# Home_automation.net
KiCad netlist of a schematic drawn in EAGLE
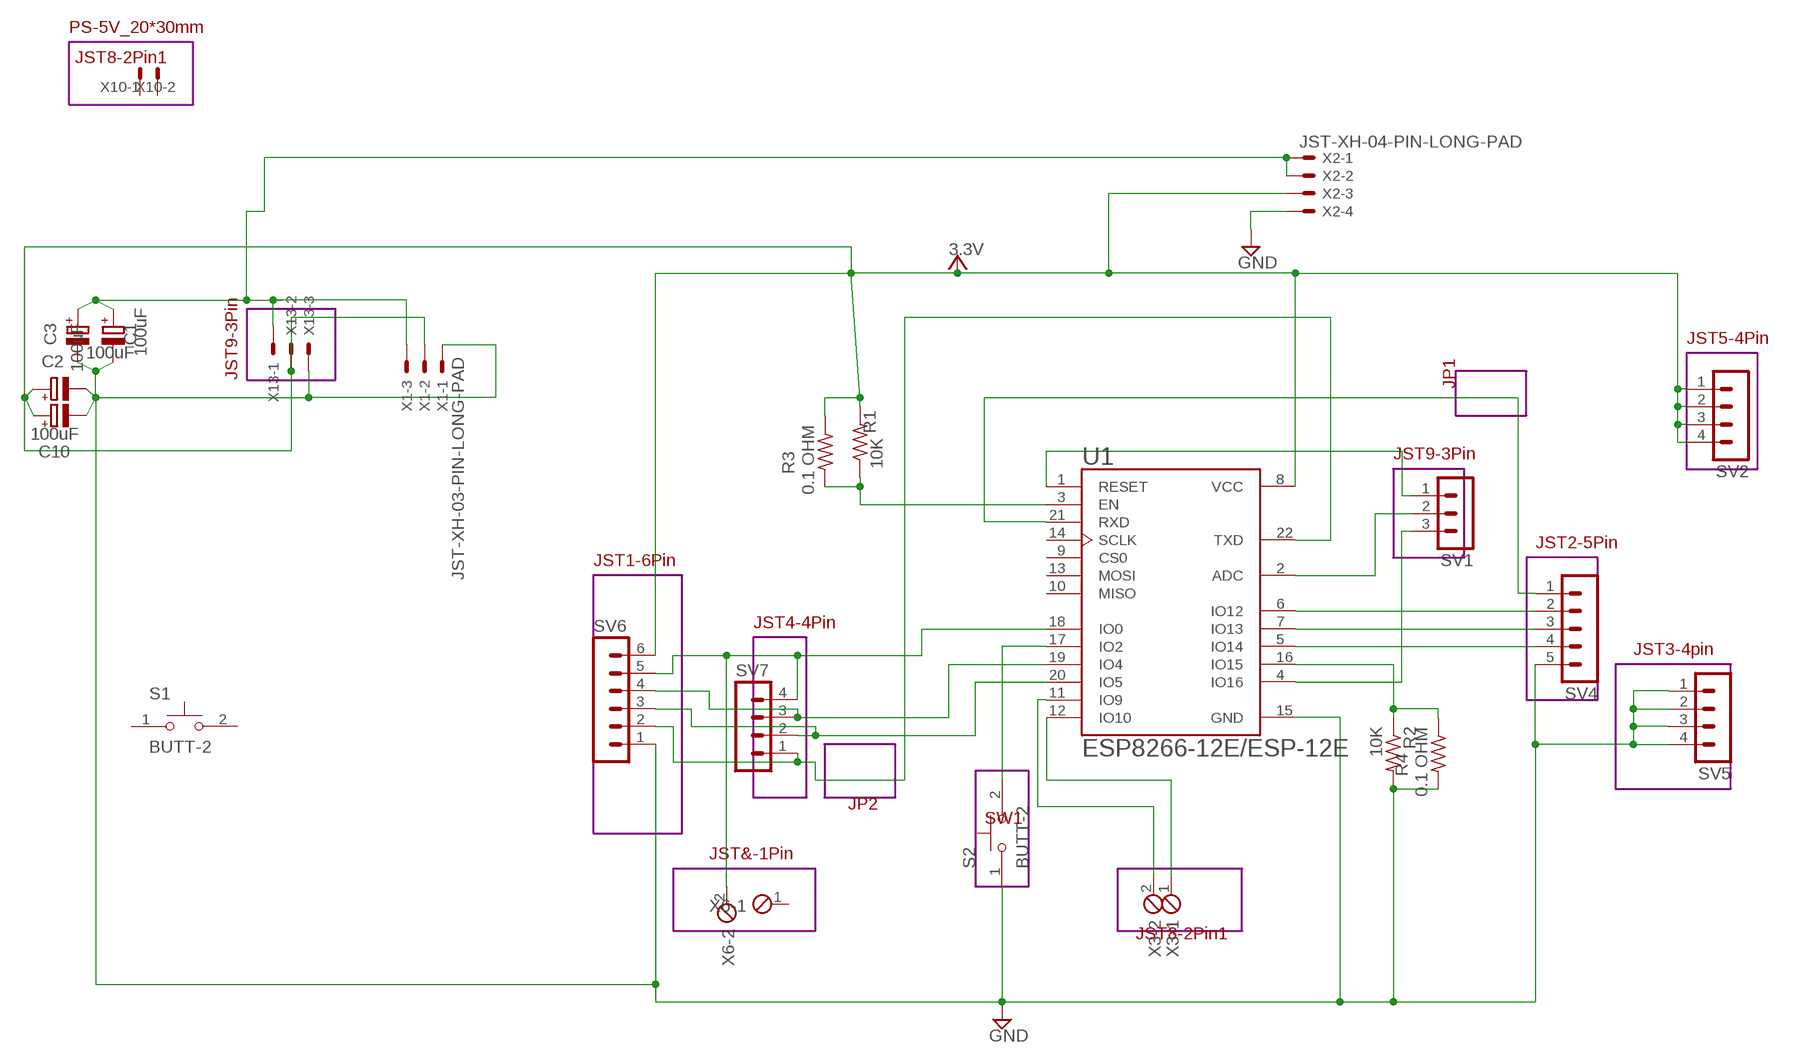
[diagram p0: schematic, sheet 1]

(export (version "E")
  (design (tool "Eeschema 10.0.6"))
  (components
    (comp (ref "C1")
      (value "100uF")
      (footprint "eagle-import:SMC_B")
      (libsource (lib "eagle-import") (part "CPOL-EUSMCB"))
    )
    (comp (ref "C2")
      (value "100uF")
      (footprint "eagle-import:E2,5-6E")
      (libsource (lib "eagle-import") (part "CPOL-EUE2,5-6E"))
    )
    (comp (ref "C3")
      (value "100uF")
      (footprint "eagle-import:E2,5-6E")
      (libsource (lib "eagle-import") (part "CPOL-EUE2,5-6E"))
    )
    (comp (ref "C10")
      (value "100uF")
      (footprint "eagle-import:SMC_B")
      (libsource (lib "eagle-import") (part "CPOL-EUSMCB"))
    )
    (comp (ref "R1")
      (value "10K")
      (footprint "eagle-import:R0805")
      (libsource (lib "eagle-import") (part "R-US_R0805"))
    )
    (comp (ref "R2")
      (value "10K")
      (footprint "eagle-import:R0805")
      (libsource (lib "eagle-import") (part "R-US_R0805"))
    )
    (comp (ref "R3")
      (value "0.1 OHM")
      (footprint "eagle-import:0207_10")
      (libsource (lib "eagle-import") (part "R-US_0207/10"))
    )
    (comp (ref "R4")
      (value "0.1 OHM")
      (footprint "eagle-import:0207_10")
      (libsource (lib "eagle-import") (part "R-US_0207/10"))
    )
    (comp (ref "S1")
      (value "BUTT-2")
      (footprint "eagle-import:SW_BUTT-2")
      (fields (field (name "MF") "Gravitech"))
      (libsource (lib "eagle-import") (part "BUTT-2__BUTT-2"))
    )
    (comp (ref "S2")
      (value "BUTT-2")
      (footprint "eagle-import:SW_BUTT-2")
      (fields (field (name "MF") "Gravitech"))
      (libsource (lib "eagle-import") (part "BUTT-2"))
    )
    (comp (ref "SV1")
      (value "MA03-1")
      (footprint "eagle-import:MA03-1")
      (libsource (lib "eagle-import") (part "MA03-1"))
    )
    (comp (ref "SV2")
      (value "MA04-1")
      (footprint "eagle-import:MA04-1")
      (libsource (lib "eagle-import") (part "MA04-1"))
    )
    (comp (ref "SV4")
      (value "MA05-1")
      (footprint "eagle-import:MA05-1")
      (libsource (lib "eagle-import") (part "MA05-1"))
    )
    (comp (ref "SV5")
      (value "MA04-1")
      (footprint "eagle-import:MA04-1")
      (libsource (lib "eagle-import") (part "MA04-1"))
    )
    (comp (ref "SV6")
      (value "MA06-1")
      (footprint "eagle-import:MA06-1")
      (libsource (lib "eagle-import") (part "MA06-1"))
    )
    (comp (ref "SV7")
      (value "MA04-1")
      (footprint "eagle-import:MA04-1")
      (libsource (lib "eagle-import") (part "MA04-1"))
    )
    (comp (ref "U1")
      (value "ESP8266-12E/ESP-12E")
      (footprint "eagle-import:XCVR_ESP8266-12E_ESP-12E")
      (fields (field (name "MF") "AI-Thinker"))
      (libsource (lib "eagle-import") (part "ESP8266-12E/ESP-12E"))
    )
    (comp (ref "X1")
      (value "JST-XH-03-PIN-LONG-PAD")
      (footprint "eagle-import:JST-XH-03-PACKAGE-LONG-PAD")
      (libsource (lib "eagle-import") (part "JST-XH-03-PIN-LONG-PAD"))
    )
    (comp (ref "X2")
      (value "JST-XH-04-PIN-LONG-PAD")
      (footprint "eagle-import:JST-XH-04-PACKAGE-LONG-PAD")
      (libsource (lib "eagle-import") (part "JST-XH-04-PIN-LONG-PAD"))
    )
    (comp (ref "X3")
      (value "MPT2")
      (footprint "eagle-import:2POL254")
      (libsource (lib "eagle-import") (part "MPT2"))
    )
    (comp (ref "X6")
      (value "MPT2")
      (footprint "eagle-import:2POL254")
      (libsource (lib "eagle-import") (part "MPT2"))
    )
    (comp (ref "X10")
      (value "JST-XH-02-PIN-LONG-PAD")
      (footprint "eagle-import:JST-XH-02-PACKAGE-LONG-PAD")
      (libsource (lib "eagle-import") (part "JST-XH-02-PIN-LONG-PAD"))
    )
    (comp (ref "X13")
      (value "JST9-3Pin")
      (footprint "eagle-import:JST-XH-03-PACKAGE-LONG-PAD")
      (libsource (lib "eagle-import") (part "JST-XH-03-PIN-LONG-PAD"))
    )
  )
  (nets
    (net (code "1") (name "3.3V") (class "Default")
      (node (ref "C10") (pin "+") (pinfunction "+_+") (pintype "passive"))
      (node (ref "C2") (pin "+") (pinfunction "+_+") (pintype "passive"))
      (node (ref "R1") (pin "2") (pinfunction "2_2") (pintype "passive"))
      (node (ref "R3") (pin "1") (pinfunction "1_1") (pintype "passive"))
      (node (ref "SV2") (pin "1") (pinfunction "1_1") (pintype "passive"))
      (node (ref "SV2") (pin "2") (pinfunction "2_2") (pintype "passive"))
      (node (ref "SV2") (pin "3") (pinfunction "3_3") (pintype "passive"))
      (node (ref "SV2") (pin "4") (pinfunction "4_4") (pintype "passive"))
      (node (ref "SV6") (pin "6") (pinfunction "6_6") (pintype "passive"))
      (node (ref "U1") (pin "8") (pinfunction "VCC_8") (pintype "power_in"))
      (node (ref "X1") (pin "2") (pinfunction "S_2") (pintype "passive"))
      (node (ref "X13") (pin "2") (pinfunction "S_2") (pintype "passive"))
      (node (ref "X2") (pin "3") (pinfunction "S_3") (pintype "passive"))
    )
    (net (code "2") (name "GND") (class "Default")
      (node (ref "C1") (pin "-") (pinfunction "-_-") (pintype "passive"))
      (node (ref "C10") (pin "-") (pinfunction "-_-") (pintype "passive"))
      (node (ref "C2") (pin "-") (pinfunction "-_-") (pintype "passive"))
      (node (ref "C3") (pin "-") (pinfunction "-_-") (pintype "passive"))
      (node (ref "R2") (pin "2") (pinfunction "2_2") (pintype "passive"))
      (node (ref "R4") (pin "2") (pinfunction "2_2") (pintype "passive"))
      (node (ref "S2") (pin "1") (pinfunction "1_1") (pintype "passive"))
      (node (ref "SV4") (pin "5") (pinfunction "5_5") (pintype "passive"))
      (node (ref "SV5") (pin "1") (pinfunction "1_1") (pintype "passive"))
      (node (ref "SV5") (pin "2") (pinfunction "2_2") (pintype "passive"))
      (node (ref "SV5") (pin "3") (pinfunction "3_3") (pintype "passive"))
      (node (ref "SV5") (pin "4") (pinfunction "4_4") (pintype "passive"))
      (node (ref "SV6") (pin "1") (pinfunction "1_1") (pintype "passive"))
      (node (ref "U1") (pin "15") (pinfunction "GND_15") (pintype "power_in"))
      (node (ref "X1") (pin "1") (pinfunction "S_1") (pintype "passive"))
      (node (ref "X13") (pin "3") (pinfunction "S_3") (pintype "passive"))
      (node (ref "X2") (pin "4") (pinfunction "S_4") (pintype "passive"))
    )
    (net (code "3") (name "Net-(U1-ADC)") (class "Default")
      (node (ref "SV1") (pin "2") (pinfunction "2_2") (pintype "passive"))
      (node (ref "U1") (pin "2") (pinfunction "ADC_2") (pintype "passive"))
    )
    (net (code "4") (name "Net-(U1-EN)") (class "Default")
      (node (ref "R1") (pin "1") (pinfunction "1_1") (pintype "passive"))
      (node (ref "R3") (pin "2") (pinfunction "2_2") (pintype "passive"))
      (node (ref "U1") (pin "3") (pinfunction "EN_3") (pintype "input"))
    )
    (net (code "5") (name "Net-(U1-IO0)") (class "Default")
      (node (ref "SV6") (pin "5") (pinfunction "5_5") (pintype "passive"))
      (node (ref "SV7") (pin "4") (pinfunction "4_4") (pintype "passive"))
      (node (ref "U1") (pin "18") (pinfunction "IO0_18") (pintype "bidirectional"))
      (node (ref "X6") (pin "2") (pinfunction "1_2") (pintype "passive"))
    )
    (net (code "6") (name "Net-(U1-IO2)") (class "Default")
      (node (ref "S2") (pin "2") (pinfunction "2_2") (pintype "passive"))
      (node (ref "U1") (pin "17") (pinfunction "IO2_17") (pintype "bidirectional"))
    )
    (net (code "7") (name "Net-(U1-IO4)") (class "Default")
      (node (ref "SV6") (pin "4") (pinfunction "4_4") (pintype "passive"))
      (node (ref "SV7") (pin "3") (pinfunction "3_3") (pintype "passive"))
      (node (ref "U1") (pin "19") (pinfunction "IO4_19") (pintype "bidirectional"))
    )
    (net (code "8") (name "Net-(U1-IO5)") (class "Default")
      (node (ref "SV6") (pin "3") (pinfunction "3_3") (pintype "passive"))
      (node (ref "SV7") (pin "2") (pinfunction "2_2") (pintype "passive"))
      (node (ref "U1") (pin "20") (pinfunction "IO5_20") (pintype "bidirectional"))
    )
    (net (code "9") (name "Net-(U1-IO9)") (class "Default")
      (node (ref "U1") (pin "11") (pinfunction "IO9_11") (pintype "bidirectional"))
      (node (ref "X3") (pin "2") (pinfunction "1_2") (pintype "passive"))
    )
    (net (code "10") (name "Net-(U1-IO10)") (class "Default")
      (node (ref "U1") (pin "12") (pinfunction "IO10_12") (pintype "bidirectional"))
      (node (ref "X3") (pin "1") (pinfunction "1_1") (pintype "passive"))
    )
    (net (code "11") (name "Net-(U1-IO12)") (class "Default")
      (node (ref "SV4") (pin "2") (pinfunction "2_2") (pintype "passive"))
      (node (ref "U1") (pin "6") (pinfunction "IO12_6") (pintype "bidirectional"))
    )
    (net (code "12") (name "Net-(U1-IO13)") (class "Default")
      (node (ref "SV4") (pin "3") (pinfunction "3_3") (pintype "passive"))
      (node (ref "U1") (pin "7") (pinfunction "IO13_7") (pintype "bidirectional"))
    )
    (net (code "13") (name "Net-(U1-IO14)") (class "Default")
      (node (ref "SV4") (pin "4") (pinfunction "4_4") (pintype "passive"))
      (node (ref "U1") (pin "5") (pinfunction "IO14_5") (pintype "bidirectional"))
    )
    (net (code "14") (name "Net-(U1-IO15)") (class "Default")
      (node (ref "R2") (pin "1") (pinfunction "1_1") (pintype "passive"))
      (node (ref "R4") (pin "1") (pinfunction "1_1") (pintype "passive"))
      (node (ref "U1") (pin "16") (pinfunction "IO15_16") (pintype "bidirectional"))
    )
    (net (code "15") (name "Net-(U1-IO16)") (class "Default")
      (node (ref "SV1") (pin "3") (pinfunction "3_3") (pintype "passive"))
      (node (ref "U1") (pin "4") (pinfunction "IO16_4") (pintype "bidirectional"))
    )
    (net (code "16") (name "Net-(U1-RESET)") (class "Default")
      (node (ref "SV1") (pin "1") (pinfunction "1_1") (pintype "passive"))
      (node (ref "U1") (pin "1") (pinfunction "RESET_1") (pintype "input"))
    )
    (net (code "17") (name "Net-(U1-RXD)") (class "Default")
      (node (ref "SV4") (pin "1") (pinfunction "1_1") (pintype "passive"))
      (node (ref "U1") (pin "21") (pinfunction "RXD_21") (pintype "input"))
    )
    (net (code "18") (name "Net-(U1-TXD)") (class "Default")
      (node (ref "SV6") (pin "2") (pinfunction "2_2") (pintype "passive"))
      (node (ref "SV7") (pin "1") (pinfunction "1_1") (pintype "passive"))
      (node (ref "U1") (pin "22") (pinfunction "TXD_22") (pintype "output"))
    )
    (net (code "19") (name "Net-(X13A-S)") (class "Default")
      (node (ref "C1") (pin "+") (pinfunction "+_+") (pintype "passive"))
      (node (ref "C3") (pin "+") (pinfunction "+_+") (pintype "passive"))
      (node (ref "X1") (pin "3") (pinfunction "S_3") (pintype "passive"))
      (node (ref "X13") (pin "1") (pinfunction "S_1") (pintype "passive"))
      (node (ref "X2") (pin "1") (pinfunction "S_1") (pintype "passive"))
      (node (ref "X2") (pin "2") (pinfunction "S_2") (pintype "passive"))
    )
    (net (code "20") (name "unconnected-(S1-Pad1)") (class "Default")
      (node (ref "S1") (pin "1") (pinfunction "1_1") (pintype "passive"))
    )
    (net (code "21") (name "unconnected-(S1-Pad2)") (class "Default")
      (node (ref "S1") (pin "2") (pinfunction "2_2") (pintype "passive"))
    )
    (net (code "22") (name "unconnected-(U1-CS0-Pad9)") (class "Default")
      (node (ref "U1") (pin "9") (pinfunction "CS0_9") (pintype "input"))
    )
    (net (code "23") (name "unconnected-(U1-MISO-Pad10)") (class "Default")
      (node (ref "U1") (pin "10") (pinfunction "MISO_10") (pintype "bidirectional"))
    )
    (net (code "24") (name "unconnected-(U1-MOSI-Pad13)") (class "Default")
      (node (ref "U1") (pin "13") (pinfunction "MOSI_13") (pintype "bidirectional"))
    )
    (net (code "25") (name "unconnected-(U1-SCLK-Pad14)") (class "Default")
      (node (ref "U1") (pin "14") (pinfunction "SCLK_14") (pintype "input"))
    )
    (net (code "26") (name "unconnected-(X6-Pad1)") (class "Default")
      (node (ref "X6") (pin "1") (pinfunction "1_1") (pintype "passive"))
    )
    (net (code "27") (name "unconnected-(X10A-S-Pad1)") (class "Default")
      (node (ref "X10") (pin "1") (pinfunction "S_1") (pintype "passive"))
    )
    (net (code "28") (name "unconnected-(X10B-S-Pad2)") (class "Default")
      (node (ref "X10") (pin "2") (pinfunction "S_2") (pintype "passive"))
    )
  )
)
